# 1-Schematic_N64_SpyDVI.net
KiCad netlist of a schematic drawn in EasyEDA
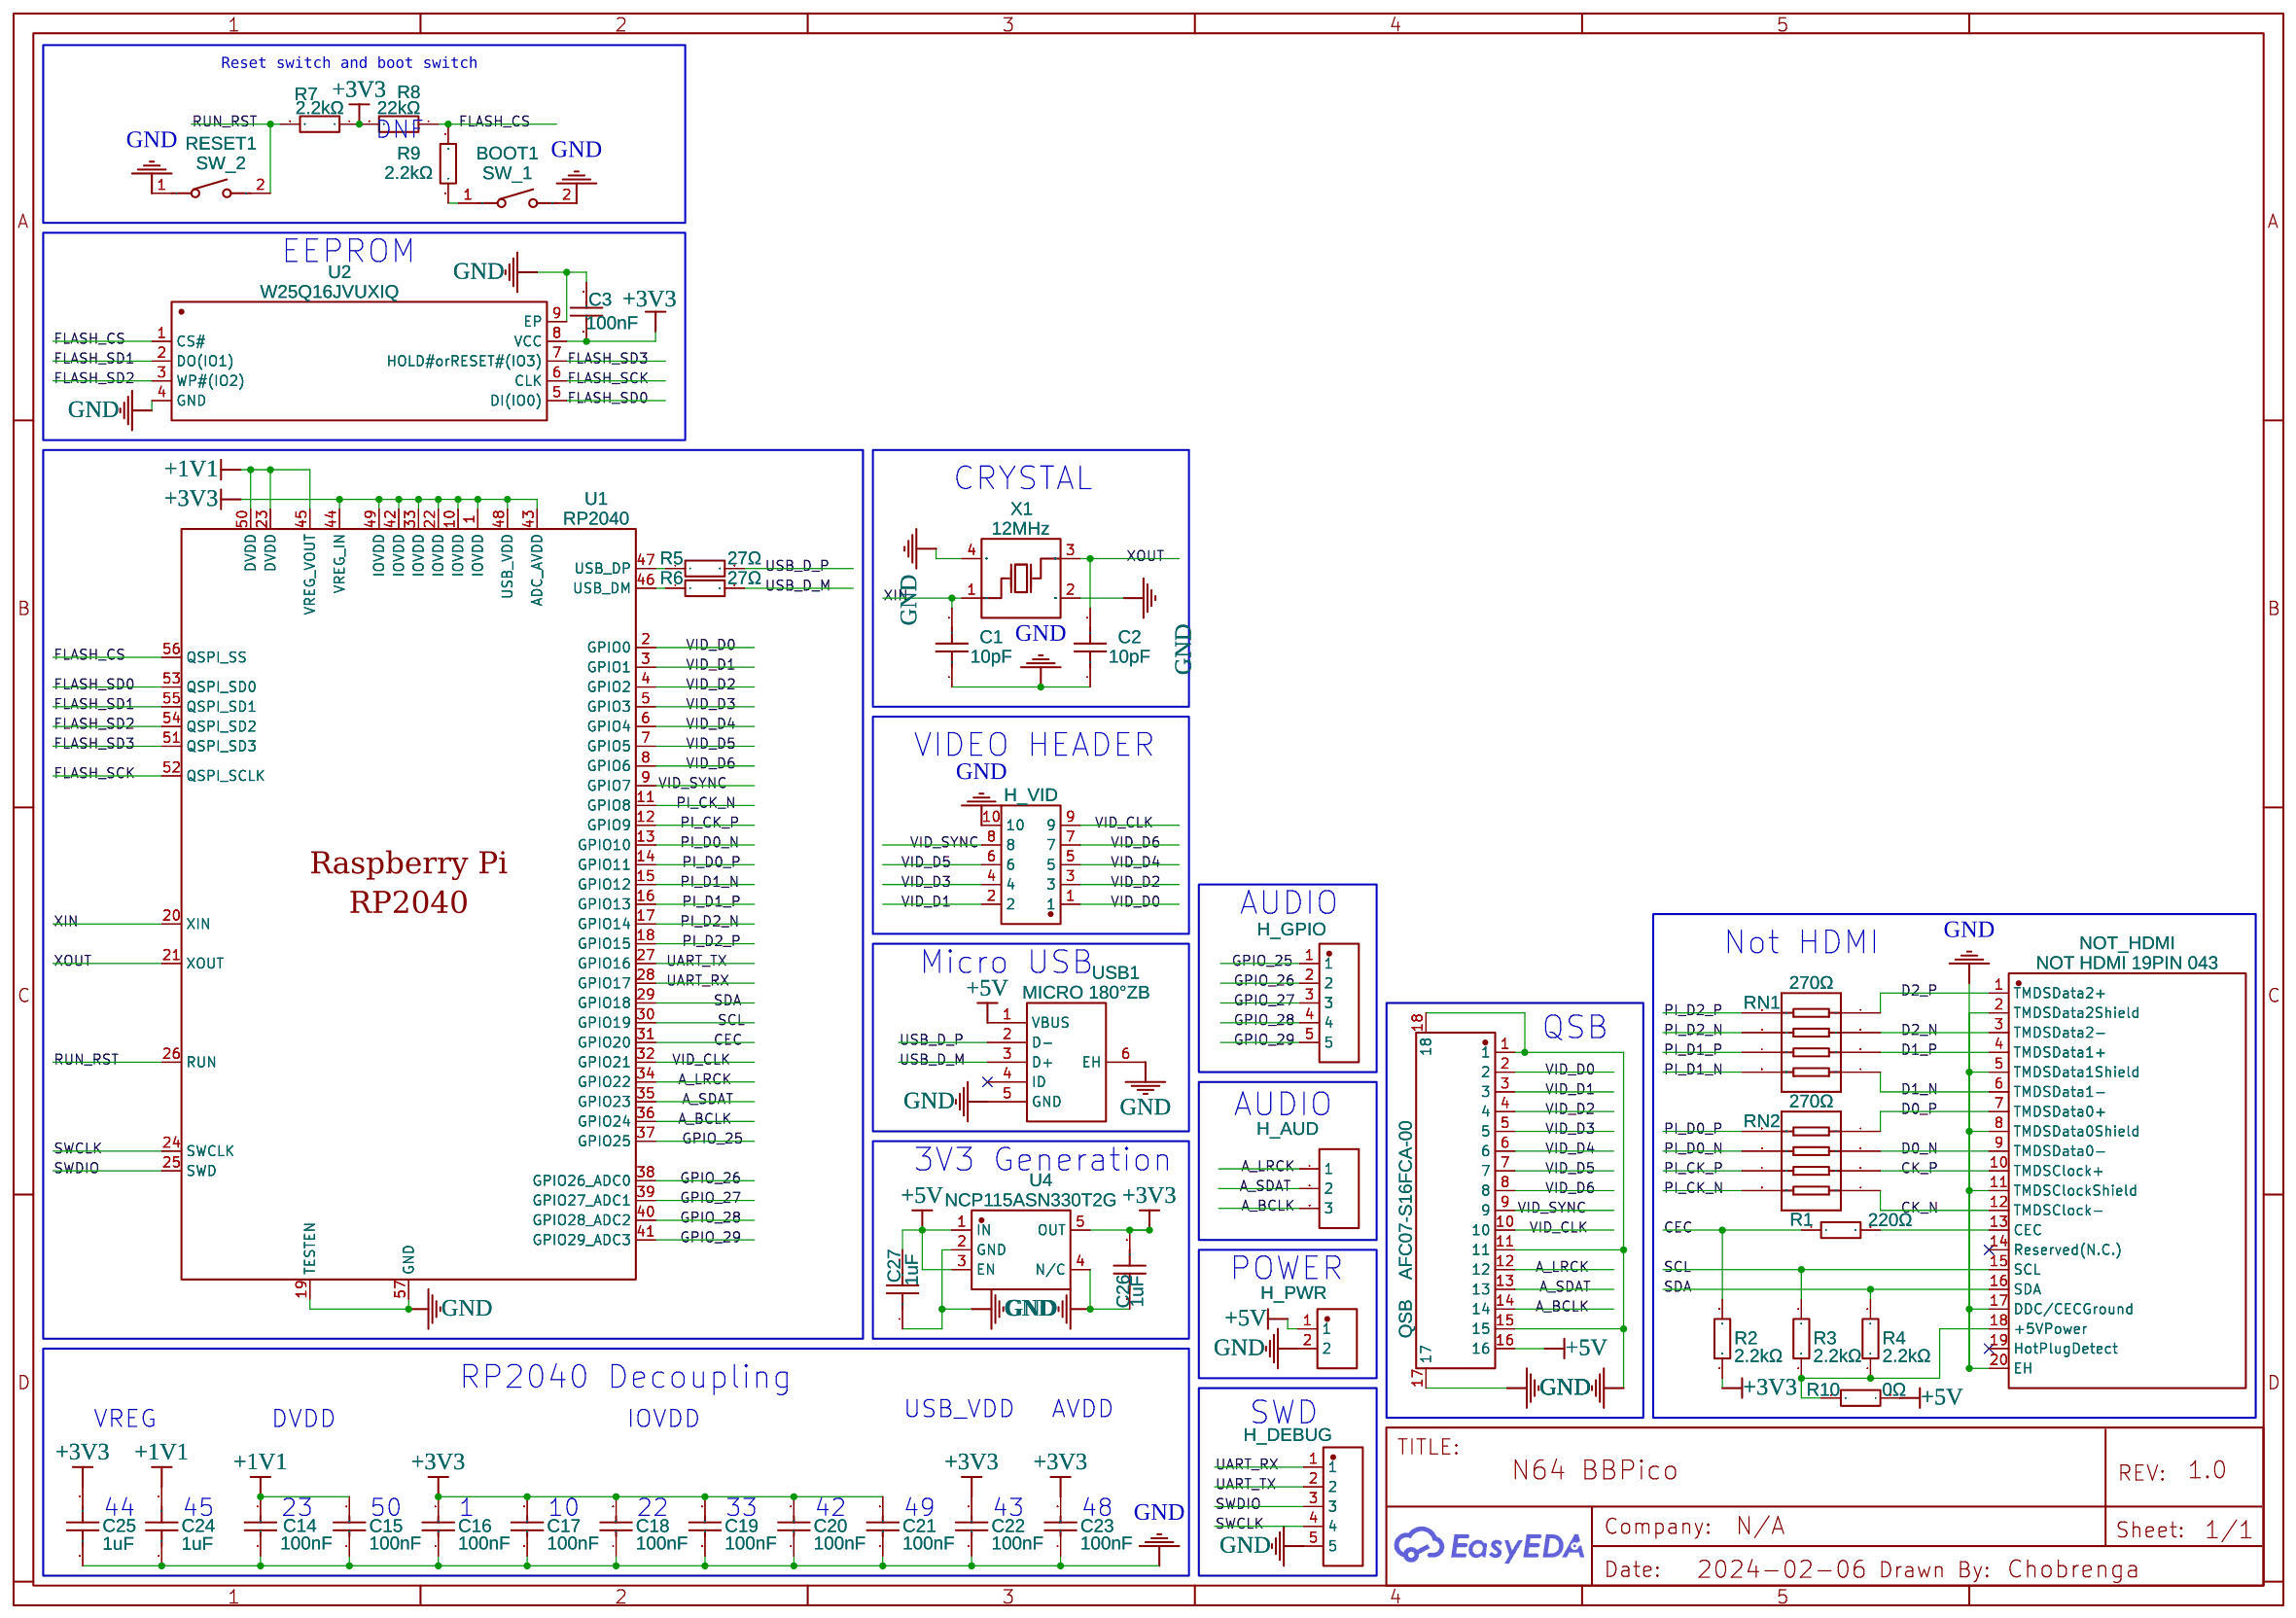
[diagram p0: schematic sheet]

(export (version "E")
  (design (tool "Eeschema 10.0.6"))
  (components
    (comp (ref "BOOT1")
      (value "SW_1")
      (fields (field (name "Manufacturer Part") "TS-1088-AR02016") (field (name "Manufacturer") "XUNPU(讯普)"))
      (libsource (lib "") (part "TS-1088-AR02016_1"))
    )
    (comp (ref "C1")
      (value "10pF")
      (fields
        (field (name "Manufacturer Part") "CL05C100JB5NNNC")
        (field (name "Manufacturer") "SAMSUNG(三星)")
      )
      (libsource (lib "") (part "CL05C100JB5NNNC"))
    )
    (comp (ref "C2")
      (value "10pF")
      (fields
        (field (name "Manufacturer Part") "CL05C100JB5NNNC")
        (field (name "Manufacturer") "SAMSUNG(三星)")
      )
      (libsource (lib "") (part "CL05C100JB5NNNC"))
    )
    (comp (ref "C3")
      (value "100nF")
      (fields
        (field (name "Manufacturer Part") "CL05B104KO5NNNC")
        (field (name "Manufacturer") "SAMSUNG(三星)")
      )
      (libsource (lib "") (part "CL05B104KO5NNNC"))
    )
    (comp (ref "C14")
      (value "100nF")
      (fields
        (field (name "Manufacturer Part") "CL05B104KO5NNNC")
        (field (name "Manufacturer") "SAMSUNG(三星)")
      )
      (libsource (lib "") (part "CL05B104KO5NNNC"))
    )
    (comp (ref "C15")
      (value "100nF")
      (fields
        (field (name "Manufacturer Part") "CL05B104KO5NNNC")
        (field (name "Manufacturer") "SAMSUNG(三星)")
      )
      (libsource (lib "") (part "CL05B104KO5NNNC"))
    )
    (comp (ref "C16")
      (value "100nF")
      (fields
        (field (name "Manufacturer Part") "CL05B104KO5NNNC")
        (field (name "Manufacturer") "SAMSUNG(三星)")
      )
      (libsource (lib "") (part "CL05B104KO5NNNC"))
    )
    (comp (ref "C17")
      (value "100nF")
      (fields
        (field (name "Manufacturer Part") "CL05B104KO5NNNC")
        (field (name "Manufacturer") "SAMSUNG(三星)")
      )
      (libsource (lib "") (part "CL05B104KO5NNNC"))
    )
    (comp (ref "C18")
      (value "100nF")
      (fields
        (field (name "Manufacturer Part") "CL05B104KO5NNNC")
        (field (name "Manufacturer") "SAMSUNG(三星)")
      )
      (libsource (lib "") (part "CL05B104KO5NNNC"))
    )
    (comp (ref "C19")
      (value "100nF")
      (fields
        (field (name "Manufacturer Part") "CL05B104KO5NNNC")
        (field (name "Manufacturer") "SAMSUNG(三星)")
      )
      (libsource (lib "") (part "CL05B104KO5NNNC"))
    )
    (comp (ref "C20")
      (value "100nF")
      (fields
        (field (name "Manufacturer Part") "CL05B104KO5NNNC")
        (field (name "Manufacturer") "SAMSUNG(三星)")
      )
      (libsource (lib "") (part "CL05B104KO5NNNC"))
    )
    (comp (ref "C21")
      (value "100nF")
      (fields
        (field (name "Manufacturer Part") "CL05B104KO5NNNC")
        (field (name "Manufacturer") "SAMSUNG(三星)")
      )
      (libsource (lib "") (part "CL05B104KO5NNNC"))
    )
    (comp (ref "C22")
      (value "100nF")
      (fields
        (field (name "Manufacturer Part") "CL05B104KO5NNNC")
        (field (name "Manufacturer") "SAMSUNG(三星)")
      )
      (libsource (lib "") (part "CL05B104KO5NNNC"))
    )
    (comp (ref "C23")
      (value "100nF")
      (fields
        (field (name "Manufacturer Part") "CL05B104KO5NNNC")
        (field (name "Manufacturer") "SAMSUNG(三星)")
      )
      (libsource (lib "") (part "CL05B104KO5NNNC"))
    )
    (comp (ref "C24")
      (value "1uF")
      (fields
        (field (name "Manufacturer Part") "TCC0402X5R105K100AT")
        (field (name "Manufacturer") "CCTC(三环)")
      )
      (libsource (lib "") (part "TCC0402X5R105K100AT"))
    )
    (comp (ref "C25")
      (value "1uF")
      (fields
        (field (name "Manufacturer Part") "TCC0402X5R105K100AT")
        (field (name "Manufacturer") "CCTC(三环)")
      )
      (libsource (lib "") (part "TCC0402X5R105K100AT"))
    )
    (comp (ref "C26")
      (value "1uF")
      (fields
        (field (name "Manufacturer Part") "TCC0402X5R105K100AT")
        (field (name "Manufacturer") "CCTC(三环)")
      )
      (libsource (lib "") (part "TCC0402X5R105K100AT"))
    )
    (comp (ref "C27")
      (value "1uF")
      (fields
        (field (name "Manufacturer Part") "TCC0402X5R105K100AT")
        (field (name "Manufacturer") "CCTC(三环)")
      )
      (libsource (lib "") (part "TCC0402X5R105K100AT"))
    )
    (comp (ref "H_AUD")
      (value "Header-Male-2.54_1x3")
      (fields (field (name "Manufacturer Part") "2.54-1*3P针") (field (name "Manufacturer") "BOOMELE(博穆精密)"))
      (libsource (lib "") (part "Header-Male-2.54_1x3"))
    )
    (comp (ref "H_DEBUG")
      (value "PZ254V-11-05P")
      (fields (field (name "Manufacturer") "XFCN(兴飞)"))
      (libsource (lib "") (part "PZ254V-11-05P"))
    )
    (comp (ref "H_GPIO")
      (value "PZ254V-11-05P")
      (fields (field (name "Manufacturer") "XFCN(兴飞)"))
      (libsource (lib "") (part "PZ254V-11-05P_1"))
    )
    (comp (ref "H_PWR")
      (value "PZ254V-11-02P")
      (fields (field (name "Manufacturer") "XFCN(兴飞)"))
      (libsource (lib "") (part "PZ254V-11-02P"))
    )
    (comp (ref "H_VID")
      (value "PZ254V-12-10P")
      (fields (field (name "Manufacturer") "XFCN(兴飞)"))
      (libsource (lib "") (part "PZ254V-12-10P"))
    )
    (comp (ref "NOT_HDMI")
      (value "NOT HDMI 19PIN 043")
      (fields
        (field (name "Manufacturer Part") "HDMI 19PIN 043")
        (field (name "Manufacturer") "SHOU HAN(首韩)")
      )
      (libsource (lib "") (part "HDMI 19PIN 043"))
    )
    (comp (ref "QSB")
      (value "AFC07-S16FCA-00")
      (fields (field (name "Manufacturer") "JS(钜硕电子)"))
      (libsource (lib "") (part "AFC07-S16FCA-00"))
    )
    (comp (ref "R1")
      (value "220Ω")
      (fields
        (field (name "Manufacturer Part") "0402WGF2200TCE")
        (field (name "Manufacturer") "UNI-ROYAL(厚声)")
      )
      (libsource (lib "") (part "0402WGF2200TCE"))
    )
    (comp (ref "R2")
      (value "2.2kΩ")
      (fields
        (field (name "Manufacturer Part") "0402WGF2201TCE")
        (field (name "Manufacturer") "UNI-ROYAL(厚声)")
      )
      (libsource (lib "") (part "0402WGF2201TCE"))
    )
    (comp (ref "R3")
      (value "2.2kΩ")
      (fields
        (field (name "Manufacturer Part") "0402WGF2201TCE")
        (field (name "Manufacturer") "UNI-ROYAL(厚声)")
      )
      (libsource (lib "") (part "0402WGF2201TCE"))
    )
    (comp (ref "R4")
      (value "2.2kΩ")
      (fields
        (field (name "Manufacturer Part") "0402WGF2201TCE")
        (field (name "Manufacturer") "UNI-ROYAL(厚声)")
      )
      (libsource (lib "") (part "0402WGF2201TCE"))
    )
    (comp (ref "R5")
      (value "27Ω")
      (fields
        (field (name "Manufacturer Part") "0402WGF270JTCE")
        (field (name "Manufacturer") "UNI-ROYAL(厚声)")
      )
      (libsource (lib "") (part "0402WGF270JTCE"))
    )
    (comp (ref "R6")
      (value "27Ω")
      (fields
        (field (name "Manufacturer Part") "0402WGF270JTCE")
        (field (name "Manufacturer") "UNI-ROYAL(厚声)")
      )
      (libsource (lib "") (part "0402WGF270JTCE"))
    )
    (comp (ref "R7")
      (value "2.2kΩ")
      (fields
        (field (name "Manufacturer Part") "0402WGF2201TCE")
        (field (name "Manufacturer") "UNI-ROYAL(厚声)")
      )
      (libsource (lib "") (part "0402WGF2201TCE_1"))
    )
    (comp (ref "R8") (value "22kΩ") (libsource (lib "") (part "0402WGF2202TCE")))
    (comp (ref "R9")
      (value "2.2kΩ")
      (fields
        (field (name "Manufacturer Part") "0402WGF2201TCE")
        (field (name "Manufacturer") "UNI-ROYAL(厚声)")
      )
      (libsource (lib "") (part "0402WGF2201TCE"))
    )
    (comp (ref "R10")
      (value "0Ω")
      (fields
        (field (name "Manufacturer Part") "0603WAF0000T5E")
        (field (name "Manufacturer") "UNI-ROYAL(厚声)")
      )
      (libsource (lib "") (part "0603WAF0000T5E"))
    )
    (comp (ref "RESET1")
      (value "SW_2")
      (fields (field (name "Manufacturer Part") "TS-1088-AR02016") (field (name "Manufacturer") "XUNPU(讯普)"))
      (libsource (lib "") (part "TS-1088-AR02016"))
    )
    (comp (ref "RN1")
      (value "270Ω")
      (fields (field (name "Manufacturer Part") "CAT10-271J4LF") (field (name "Manufacturer") "BOURNS"))
      (libsource (lib "") (part "CAT10-271J4LF"))
    )
    (comp (ref "RN2")
      (value "270Ω")
      (fields (field (name "Manufacturer Part") "CAT10-271J4LF") (field (name "Manufacturer") "BOURNS"))
      (libsource (lib "") (part "CAT10-271J4LF"))
    )
    (comp (ref "U1")
      (value "RP2040")
      (fields (field (name "Manufacturer") "Raspberry Pi(树莓派)"))
      (libsource (lib "") (part "RP2040"))
    )
    (comp (ref "U2")
      (value "W25Q16JVUXIQ")
      (fields (field (name "Manufacturer") "WINBOND(华邦)"))
      (libsource (lib "") (part "W25Q16JVUXIQ"))
    )
    (comp (ref "U4")
      (value "NCP115ASN330T2G")
      (fields (field (name "Manufacturer") "onsemi(安森美)"))
      (libsource (lib "") (part "NCP115ASN330T2G"))
    )
    (comp (ref "USB1")
      (value "MICRO 180°ZB")
      (fields (field (name "Manufacturer") "SHOU HAN(首韩)"))
      (libsource (lib "") (part "MICRO 180°ZB"))
    )
    (comp (ref "X1")
      (value "12MHz")
      (fields (field (name "Manufacturer Part") "X322512MMB4SI") (field (name "Manufacturer") "YXC(扬兴晶振)"))
      (libsource (lib "") (part "X322512MMB4SI"))
    )
  )
  (nets
    (net (code "1") (name "+1V1") (class "Default")
      (node (ref "C14") (pin "2") (pinfunction "2_2") (pintype "input"))
      (node (ref "C15") (pin "2") (pinfunction "2_2") (pintype "input"))
      (node (ref "C24") (pin "2") (pinfunction "2_2") (pintype "unspecified"))
      (node (ref "U1") (pin "23") (pinfunction "DVDD_23") (pintype "bidirectional"))
      (node (ref "U1") (pin "45") (pinfunction "VREG_VOUT_45") (pintype "bidirectional"))
      (node (ref "U1") (pin "50") (pinfunction "DVDD_50") (pintype "bidirectional"))
    )
    (net (code "2") (name "+3V3") (class "Default")
      (node (ref "C16") (pin "2") (pinfunction "2_2") (pintype "input"))
      (node (ref "C17") (pin "2") (pinfunction "2_2") (pintype "input"))
      (node (ref "C18") (pin "2") (pinfunction "2_2") (pintype "input"))
      (node (ref "C19") (pin "2") (pinfunction "2_2") (pintype "input"))
      (node (ref "C20") (pin "2") (pinfunction "2_2") (pintype "input"))
      (node (ref "C21") (pin "2") (pinfunction "2_2") (pintype "input"))
      (node (ref "C22") (pin "2") (pinfunction "2_2") (pintype "input"))
      (node (ref "C23") (pin "2") (pinfunction "2_2") (pintype "input"))
      (node (ref "C25") (pin "2") (pinfunction "2_2") (pintype "unspecified"))
      (node (ref "C26") (pin "2") (pinfunction "2_2") (pintype "unspecified"))
      (node (ref "C3") (pin "1") (pinfunction "1_1") (pintype "input"))
      (node (ref "R2") (pin "1") (pinfunction "1_1") (pintype "input"))
      (node (ref "R7") (pin "1") (pinfunction "1_1") (pintype "input"))
      (node (ref "R8") (pin "2") (pinfunction "2_2") (pintype "input"))
      (node (ref "U1") (pin "1") (pinfunction "IOVDD_1") (pintype "bidirectional"))
      (node (ref "U1") (pin "10") (pinfunction "IOVDD_10") (pintype "bidirectional"))
      (node (ref "U1") (pin "22") (pinfunction "IOVDD_22") (pintype "bidirectional"))
      (node (ref "U1") (pin "33") (pinfunction "IOVDD_33") (pintype "bidirectional"))
      (node (ref "U1") (pin "42") (pinfunction "IOVDD_42") (pintype "bidirectional"))
      (node (ref "U1") (pin "43") (pinfunction "ADC_AVDD_43") (pintype "bidirectional"))
      (node (ref "U1") (pin "44") (pinfunction "VREG_IN_44") (pintype "bidirectional"))
      (node (ref "U1") (pin "48") (pinfunction "USB_VDD_48") (pintype "bidirectional"))
      (node (ref "U1") (pin "49") (pinfunction "IOVDD_49") (pintype "bidirectional"))
      (node (ref "U2") (pin "8") (pinfunction "VCC_8") (pintype "unspecified"))
      (node (ref "U4") (pin "5") (pinfunction "OUT_5") (pintype "unspecified"))
    )
    (net (code "3") (name "+5V") (class "Default")
      (node (ref "C27") (pin "2") (pinfunction "2_2") (pintype "unspecified"))
      (node (ref "H_PWR") (pin "1") (pinfunction "1_1") (pintype "unspecified"))
      (node (ref "QSB") (pin "16") (pinfunction "16_16") (pintype "unspecified"))
      (node (ref "R10") (pin "1") (pinfunction "1_1") (pintype "input"))
      (node (ref "U4") (pin "1") (pinfunction "IN_1") (pintype "unspecified"))
      (node (ref "U4") (pin "3") (pinfunction "EN_3") (pintype "unspecified"))
      (node (ref "USB1") (pin "1") (pinfunction "VBUS_1") (pintype "unspecified"))
    )
    (net (code "4") (name "/A_BCLK") (class "Default")
      (node (ref "H_AUD") (pin "3") (pinfunction "3_3") (pintype "input"))
      (node (ref "QSB") (pin "14") (pinfunction "14_14") (pintype "unspecified"))
      (node (ref "U1") (pin "36") (pinfunction "GPIO24_36") (pintype "bidirectional"))
    )
    (net (code "5") (name "/A_LRCK") (class "Default")
      (node (ref "H_AUD") (pin "1") (pinfunction "1_1") (pintype "input"))
      (node (ref "QSB") (pin "12") (pinfunction "12_12") (pintype "unspecified"))
      (node (ref "U1") (pin "34") (pinfunction "GPIO22_34") (pintype "bidirectional"))
    )
    (net (code "6") (name "/A_SDAT") (class "Default")
      (node (ref "H_AUD") (pin "2") (pinfunction "2_2") (pintype "input"))
      (node (ref "QSB") (pin "13") (pinfunction "13_13") (pintype "unspecified"))
      (node (ref "U1") (pin "35") (pinfunction "GPIO23_35") (pintype "bidirectional"))
    )
    (net (code "7") (name "/CEC") (class "Default")
      (node (ref "R1") (pin "1") (pinfunction "1_1") (pintype "input"))
      (node (ref "R2") (pin "2") (pinfunction "2_2") (pintype "input"))
      (node (ref "U1") (pin "31") (pinfunction "GPIO20_31") (pintype "bidirectional"))
    )
    (net (code "8") (name "/CK_N") (class "Default")
      (node (ref "NOT_HDMI") (pin "12") (pinfunction "TMDSClock-_12") (pintype "unspecified"))
      (node (ref "RN2") (pin "1") (pinfunction "1_1") (pintype "input"))
    )
    (net (code "9") (name "/CK_P") (class "Default")
      (node (ref "NOT_HDMI") (pin "10") (pinfunction "TMDSClock+_10") (pintype "unspecified"))
      (node (ref "RN2") (pin "2") (pinfunction "2_2") (pintype "input"))
    )
    (net (code "10") (name "/D0_N") (class "Default")
      (node (ref "NOT_HDMI") (pin "9") (pinfunction "TMDSData0-_9") (pintype "unspecified"))
      (node (ref "RN2") (pin "3") (pinfunction "3_3") (pintype "input"))
    )
    (net (code "11") (name "/D0_P") (class "Default")
      (node (ref "NOT_HDMI") (pin "7") (pinfunction "TMDSData0+_7") (pintype "unspecified"))
      (node (ref "RN2") (pin "4") (pinfunction "4_4") (pintype "input"))
    )
    (net (code "12") (name "/D1_N") (class "Default")
      (node (ref "NOT_HDMI") (pin "6") (pinfunction "TMDSData1-_6") (pintype "unspecified"))
      (node (ref "RN1") (pin "1") (pinfunction "1_1") (pintype "input"))
    )
    (net (code "13") (name "/D1_P") (class "Default")
      (node (ref "NOT_HDMI") (pin "4") (pinfunction "TMDSData1+_4") (pintype "unspecified"))
      (node (ref "RN1") (pin "2") (pinfunction "2_2") (pintype "input"))
    )
    (net (code "14") (name "/D2_N") (class "Default")
      (node (ref "NOT_HDMI") (pin "3") (pinfunction "TMDSData2-_3") (pintype "unspecified"))
      (node (ref "RN1") (pin "3") (pinfunction "3_3") (pintype "input"))
    )
    (net (code "15") (name "/D2_P") (class "Default")
      (node (ref "NOT_HDMI") (pin "1") (pinfunction "TMDSData2+_1") (pintype "unspecified"))
      (node (ref "RN1") (pin "4") (pinfunction "4_4") (pintype "input"))
    )
    (net (code "16") (name "/FLASH_CS") (class "Default")
      (node (ref "R8") (pin "1") (pinfunction "1_1") (pintype "input"))
      (node (ref "R9") (pin "2") (pinfunction "2_2") (pintype "input"))
      (node (ref "U1") (pin "56") (pinfunction "QSPI_SS_56") (pintype "bidirectional"))
      (node (ref "U2") (pin "1") (pinfunction "CS#_1") (pintype "unspecified"))
    )
    (net (code "17") (name "/FLASH_SCK") (class "Default")
      (node (ref "U1") (pin "52") (pinfunction "QSPI_SCLK_52") (pintype "output"))
      (node (ref "U2") (pin "6") (pinfunction "CLK_6") (pintype "unspecified"))
    )
    (net (code "18") (name "/FLASH_SD0") (class "Default")
      (node (ref "U1") (pin "53") (pinfunction "QSPI_SD0_53") (pintype "bidirectional"))
      (node (ref "U2") (pin "5") (pinfunction "DI(IO0)_5") (pintype "unspecified"))
    )
    (net (code "19") (name "/FLASH_SD1") (class "Default")
      (node (ref "U1") (pin "55") (pinfunction "QSPI_SD1_55") (pintype "bidirectional"))
      (node (ref "U2") (pin "2") (pinfunction "DO(IO1)_2") (pintype "unspecified"))
    )
    (net (code "20") (name "/FLASH_SD2") (class "Default")
      (node (ref "U1") (pin "54") (pinfunction "QSPI_SD2_54") (pintype "bidirectional"))
      (node (ref "U2") (pin "3") (pinfunction "WP#(IO2)_3") (pintype "unspecified"))
    )
    (net (code "21") (name "/FLASH_SD3") (class "Default")
      (node (ref "U1") (pin "51") (pinfunction "QSPI_SD3_51") (pintype "bidirectional"))
      (node (ref "U2") (pin "7") (pinfunction "HOLD#orRESET#(IO3)_7") (pintype "unspecified"))
    )
    (net (code "22") (name "/GPIO_25") (class "Default")
      (node (ref "H_GPIO") (pin "1") (pinfunction "1_1") (pintype "unspecified"))
      (node (ref "U1") (pin "37") (pinfunction "GPIO25_37") (pintype "bidirectional"))
    )
    (net (code "23") (name "/GPIO_26") (class "Default")
      (node (ref "H_GPIO") (pin "2") (pinfunction "2_2") (pintype "unspecified"))
      (node (ref "U1") (pin "38") (pinfunction "GPIO26_ADC0_38") (pintype "bidirectional"))
    )
    (net (code "24") (name "/GPIO_27") (class "Default")
      (node (ref "H_GPIO") (pin "3") (pinfunction "3_3") (pintype "unspecified"))
      (node (ref "U1") (pin "39") (pinfunction "GPIO27_ADC1_39") (pintype "bidirectional"))
    )
    (net (code "25") (name "/GPIO_28") (class "Default")
      (node (ref "H_GPIO") (pin "4") (pinfunction "4_4") (pintype "unspecified"))
      (node (ref "U1") (pin "40") (pinfunction "GPIO28_ADC2_40") (pintype "bidirectional"))
    )
    (net (code "26") (name "/GPIO_29") (class "Default")
      (node (ref "H_GPIO") (pin "5") (pinfunction "5_5") (pintype "unspecified"))
      (node (ref "U1") (pin "41") (pinfunction "GPIO29_ADC3_41") (pintype "bidirectional"))
    )
    (net (code "27") (name "/PI_CK_N") (class "Default")
      (node (ref "RN2") (pin "8") (pinfunction "8_8") (pintype "input"))
      (node (ref "U1") (pin "11") (pinfunction "GPIO8_11") (pintype "bidirectional"))
    )
    (net (code "28") (name "/PI_CK_P") (class "Default")
      (node (ref "RN2") (pin "7") (pinfunction "7_7") (pintype "input"))
      (node (ref "U1") (pin "12") (pinfunction "GPIO9_12") (pintype "bidirectional"))
    )
    (net (code "29") (name "/PI_D0_N") (class "Default")
      (node (ref "RN2") (pin "6") (pinfunction "6_6") (pintype "input"))
      (node (ref "U1") (pin "13") (pinfunction "GPIO10_13") (pintype "bidirectional"))
    )
    (net (code "30") (name "/PI_D0_P") (class "Default")
      (node (ref "RN2") (pin "5") (pinfunction "5_5") (pintype "input"))
      (node (ref "U1") (pin "14") (pinfunction "GPIO11_14") (pintype "bidirectional"))
    )
    (net (code "31") (name "/PI_D1_N") (class "Default")
      (node (ref "RN1") (pin "8") (pinfunction "8_8") (pintype "input"))
      (node (ref "U1") (pin "15") (pinfunction "GPIO12_15") (pintype "bidirectional"))
    )
    (net (code "32") (name "/PI_D1_P") (class "Default")
      (node (ref "RN1") (pin "7") (pinfunction "7_7") (pintype "input"))
      (node (ref "U1") (pin "16") (pinfunction "GPIO13_16") (pintype "bidirectional"))
    )
    (net (code "33") (name "/PI_D2_N") (class "Default")
      (node (ref "RN1") (pin "6") (pinfunction "6_6") (pintype "input"))
      (node (ref "U1") (pin "17") (pinfunction "GPIO14_17") (pintype "bidirectional"))
    )
    (net (code "34") (name "/PI_D2_P") (class "Default")
      (node (ref "RN1") (pin "5") (pinfunction "5_5") (pintype "input"))
      (node (ref "U1") (pin "18") (pinfunction "GPIO15_18") (pintype "bidirectional"))
    )
    (net (code "35") (name "/RUN_RST") (class "Default")
      (node (ref "R7") (pin "2") (pinfunction "2_2") (pintype "input"))
      (node (ref "RESET1") (pin "2") (pinfunction "2_2") (pintype "unspecified"))
      (node (ref "U1") (pin "26") (pinfunction "RUN_26") (pintype "input"))
    )
    (net (code "36") (name "/SCL") (class "Default")
      (node (ref "NOT_HDMI") (pin "15") (pinfunction "SCL_15") (pintype "unspecified"))
      (node (ref "R3") (pin "2") (pinfunction "2_2") (pintype "input"))
      (node (ref "U1") (pin "30") (pinfunction "GPIO19_30") (pintype "bidirectional"))
    )
    (net (code "37") (name "/SDA") (class "Default")
      (node (ref "NOT_HDMI") (pin "16") (pinfunction "SDA_16") (pintype "unspecified"))
      (node (ref "R4") (pin "2") (pinfunction "2_2") (pintype "input"))
      (node (ref "U1") (pin "29") (pinfunction "GPIO18_29") (pintype "bidirectional"))
    )
    (net (code "38") (name "/SWCLK") (class "Default")
      (node (ref "H_DEBUG") (pin "4") (pinfunction "4_4") (pintype "unspecified"))
      (node (ref "U1") (pin "24") (pinfunction "SWCLK_24") (pintype "output"))
    )
    (net (code "39") (name "/SWDIO") (class "Default")
      (node (ref "H_DEBUG") (pin "3") (pinfunction "3_3") (pintype "unspecified"))
      (node (ref "U1") (pin "25") (pinfunction "SWD_25") (pintype "bidirectional"))
    )
    (net (code "40") (name "/UART_RX") (class "Default")
      (node (ref "H_DEBUG") (pin "1") (pinfunction "1_1") (pintype "unspecified"))
      (node (ref "U1") (pin "28") (pinfunction "GPIO17_28") (pintype "bidirectional"))
    )
    (net (code "41") (name "/UART_TX") (class "Default")
      (node (ref "H_DEBUG") (pin "2") (pinfunction "2_2") (pintype "unspecified"))
      (node (ref "U1") (pin "27") (pinfunction "GPIO16_27") (pintype "bidirectional"))
    )
    (net (code "42") (name "/USB_D_M") (class "Default")
      (node (ref "R6") (pin "2") (pinfunction "2_2") (pintype "input"))
      (node (ref "USB1") (pin "3") (pinfunction "D+_3") (pintype "unspecified"))
    )
    (net (code "43") (name "/USB_D_P") (class "Default")
      (node (ref "R5") (pin "2") (pinfunction "2_2") (pintype "input"))
      (node (ref "USB1") (pin "2") (pinfunction "D-_2") (pintype "unspecified"))
    )
    (net (code "44") (name "/VID_CLK") (class "Default")
      (node (ref "H_VID") (pin "9") (pinfunction "9_9") (pintype "unspecified"))
      (node (ref "QSB") (pin "10") (pinfunction "10_10") (pintype "unspecified"))
      (node (ref "U1") (pin "32") (pinfunction "GPIO21_32") (pintype "bidirectional"))
    )
    (net (code "45") (name "/VID_D0") (class "Default")
      (node (ref "H_VID") (pin "1") (pinfunction "1_1") (pintype "unspecified"))
      (node (ref "QSB") (pin "2") (pinfunction "2_2") (pintype "unspecified"))
      (node (ref "U1") (pin "2") (pinfunction "GPIO0_2") (pintype "bidirectional"))
    )
    (net (code "46") (name "/VID_D1") (class "Default")
      (node (ref "H_VID") (pin "2") (pinfunction "2_2") (pintype "unspecified"))
      (node (ref "QSB") (pin "3") (pinfunction "3_3") (pintype "unspecified"))
      (node (ref "U1") (pin "3") (pinfunction "GPIO1_3") (pintype "bidirectional"))
    )
    (net (code "47") (name "/VID_D2") (class "Default")
      (node (ref "H_VID") (pin "3") (pinfunction "3_3") (pintype "unspecified"))
      (node (ref "QSB") (pin "4") (pinfunction "4_4") (pintype "unspecified"))
      (node (ref "U1") (pin "4") (pinfunction "GPIO2_4") (pintype "bidirectional"))
    )
    (net (code "48") (name "/VID_D3") (class "Default")
      (node (ref "H_VID") (pin "4") (pinfunction "4_4") (pintype "unspecified"))
      (node (ref "QSB") (pin "5") (pinfunction "5_5") (pintype "unspecified"))
      (node (ref "U1") (pin "5") (pinfunction "GPIO3_5") (pintype "bidirectional"))
    )
    (net (code "49") (name "/VID_D4") (class "Default")
      (node (ref "H_VID") (pin "5") (pinfunction "5_5") (pintype "unspecified"))
      (node (ref "QSB") (pin "6") (pinfunction "6_6") (pintype "unspecified"))
      (node (ref "U1") (pin "6") (pinfunction "GPIO4_6") (pintype "bidirectional"))
    )
    (net (code "50") (name "/VID_D5") (class "Default")
      (node (ref "H_VID") (pin "6") (pinfunction "6_6") (pintype "unspecified"))
      (node (ref "QSB") (pin "7") (pinfunction "7_7") (pintype "unspecified"))
      (node (ref "U1") (pin "7") (pinfunction "GPIO5_7") (pintype "bidirectional"))
    )
    (net (code "51") (name "/VID_D6") (class "Default")
      (node (ref "H_VID") (pin "7") (pinfunction "7_7") (pintype "unspecified"))
      (node (ref "QSB") (pin "8") (pinfunction "8_8") (pintype "unspecified"))
      (node (ref "U1") (pin "8") (pinfunction "GPIO6_8") (pintype "bidirectional"))
    )
    (net (code "52") (name "/VID_SYNC") (class "Default")
      (node (ref "H_VID") (pin "8") (pinfunction "8_8") (pintype "unspecified"))
      (node (ref "QSB") (pin "9") (pinfunction "9_9") (pintype "unspecified"))
      (node (ref "U1") (pin "9") (pinfunction "GPIO7_9") (pintype "bidirectional"))
    )
    (net (code "53") (name "/XIN") (class "Default")
      (node (ref "C1") (pin "2") (pinfunction "2_2") (pintype "unspecified"))
      (node (ref "U1") (pin "20") (pinfunction "XIN_20") (pintype "input"))
      (node (ref "X1") (pin "1") (pinfunction "OSC1_1") (pintype "unspecified"))
    )
    (net (code "54") (name "/XOUT") (class "Default")
      (node (ref "C2") (pin "2") (pinfunction "2_2") (pintype "unspecified"))
      (node (ref "U1") (pin "21") (pinfunction "XOUT_21") (pintype "unspecified"))
      (node (ref "X1") (pin "3") (pinfunction "OSC2_3") (pintype "unspecified"))
    )
    (net (code "55") (name "GND") (class "Default")
      (node (ref "BOOT1") (pin "2") (pinfunction "2_2") (pintype "unspecified"))
      (node (ref "C1") (pin "1") (pinfunction "1_1") (pintype "unspecified"))
      (node (ref "C14") (pin "1") (pinfunction "1_1") (pintype "input"))
      (node (ref "C15") (pin "1") (pinfunction "1_1") (pintype "input"))
      (node (ref "C16") (pin "1") (pinfunction "1_1") (pintype "input"))
      (node (ref "C17") (pin "1") (pinfunction "1_1") (pintype "input"))
      (node (ref "C18") (pin "1") (pinfunction "1_1") (pintype "input"))
      (node (ref "C19") (pin "1") (pinfunction "1_1") (pintype "input"))
      (node (ref "C2") (pin "1") (pinfunction "1_1") (pintype "unspecified"))
      (node (ref "C20") (pin "1") (pinfunction "1_1") (pintype "input"))
      (node (ref "C21") (pin "1") (pinfunction "1_1") (pintype "input"))
      (node (ref "C22") (pin "1") (pinfunction "1_1") (pintype "input"))
      (node (ref "C23") (pin "1") (pinfunction "1_1") (pintype "input"))
      (node (ref "C24") (pin "1") (pinfunction "1_1") (pintype "unspecified"))
      (node (ref "C25") (pin "1") (pinfunction "1_1") (pintype "unspecified"))
      (node (ref "C26") (pin "1") (pinfunction "1_1") (pintype "unspecified"))
      (node (ref "C27") (pin "1") (pinfunction "1_1") (pintype "unspecified"))
      (node (ref "C3") (pin "2") (pinfunction "2_2") (pintype "input"))
      (node (ref "H_DEBUG") (pin "5") (pinfunction "5_5") (pintype "unspecified"))
      (node (ref "H_PWR") (pin "2") (pinfunction "2_2") (pintype "unspecified"))
      (node (ref "H_VID") (pin "10") (pinfunction "10_10") (pintype "unspecified"))
      (node (ref "NOT_HDMI") (pin "11") (pinfunction "TMDSClockShield_11") (pintype "unspecified"))
      (node (ref "NOT_HDMI") (pin "17") (pinfunction "DDC/CECGround_17") (pintype "unspecified"))
      (node (ref "NOT_HDMI") (pin "2") (pinfunction "TMDSData2Shield_2") (pintype "unspecified"))
      (node (ref "NOT_HDMI") (pin "20") (pinfunction "EH_20") (pintype "unspecified"))
      (node (ref "NOT_HDMI") (pin "5") (pinfunction "TMDSData1Shield_5") (pintype "unspecified"))
      (node (ref "NOT_HDMI") (pin "8") (pinfunction "TMDSData0Shield_8") (pintype "unspecified"))
      (node (ref "QSB") (pin "1") (pinfunction "1_1") (pintype "unspecified"))
      (node (ref "QSB") (pin "11") (pinfunction "11_11") (pintype "unspecified"))
      (node (ref "QSB") (pin "15") (pinfunction "15_15") (pintype "unspecified"))
      (node (ref "QSB") (pin "17") (pinfunction "17_17") (pintype "unspecified"))
      (node (ref "QSB") (pin "18") (pinfunction "18_18") (pintype "unspecified"))
      (node (ref "RESET1") (pin "1") (pinfunction "1_1") (pintype "unspecified"))
      (node (ref "U1") (pin "19") (pinfunction "TESTEN_19") (pintype "unspecified"))
      (node (ref "U1") (pin "57") (pinfunction "GND_57") (pintype "bidirectional"))
      (node (ref "U2") (pin "4") (pinfunction "GND_4") (pintype "unspecified"))
      (node (ref "U2") (pin "9") (pinfunction "EP_9") (pintype "unspecified"))
      (node (ref "U4") (pin "2") (pinfunction "GND_2") (pintype "unspecified"))
      (node (ref "U4") (pin "4") (pinfunction "N/C_4") (pintype "unspecified"))
      (node (ref "USB1") (pin "5") (pinfunction "GND_5") (pintype "unspecified"))
      (node (ref "USB1") (pin "6") (pinfunction "EH_6") (pintype "unspecified"))
      (node (ref "X1") (pin "2") (pinfunction "GND_2") (pintype "unspecified"))
      (node (ref "X1") (pin "4") (pinfunction "GND_4") (pintype "unspecified"))
    )
    (net (code "56") (name "Net-(BOOT1-Pad1)") (class "Default")
      (node (ref "BOOT1") (pin "1") (pinfunction "1_1") (pintype "unspecified"))
      (node (ref "R9") (pin "1") (pinfunction "1_1") (pintype "input"))
    )
    (net (code "57") (name "Net-(NOT_HDMI-+5VPower)") (class "Default")
      (node (ref "NOT_HDMI") (pin "18") (pinfunction "+5VPower_18") (pintype "unspecified"))
      (node (ref "R10") (pin "2") (pinfunction "2_2") (pintype "input"))
      (node (ref "R3") (pin "1") (pinfunction "1_1") (pintype "input"))
      (node (ref "R4") (pin "1") (pinfunction "1_1") (pintype "input"))
    )
    (net (code "58") (name "Net-(NOT_HDMI-CEC)") (class "Default")
      (node (ref "NOT_HDMI") (pin "13") (pinfunction "CEC_13") (pintype "unspecified"))
      (node (ref "R1") (pin "2") (pinfunction "2_2") (pintype "input"))
    )
    (net (code "59") (name "Net-(U1-USB_DM)") (class "Default")
      (node (ref "R6") (pin "1") (pinfunction "1_1") (pintype "input"))
      (node (ref "U1") (pin "46") (pinfunction "USB_DM_46") (pintype "bidirectional"))
    )
    (net (code "60") (name "Net-(U1-USB_DP)") (class "Default")
      (node (ref "R5") (pin "1") (pinfunction "1_1") (pintype "input"))
      (node (ref "U1") (pin "47") (pinfunction "USB_DP_47") (pintype "bidirectional"))
    )
    (net (code "61") (name "unconnected-(NOT_HDMI-HotPlugDetect-Pad19)") (class "Default")
      (node (ref "NOT_HDMI") (pin "19") (pinfunction "HotPlugDetect_19") (pintype "unspecified+no_connect"))
    )
    (net (code "62") (name "unconnected-(NOT_HDMI-Reserved(N.C.)-Pad14)") (class "Default")
      (node (ref "NOT_HDMI") (pin "14") (pinfunction "Reserved(N.C.)_14") (pintype "unspecified+no_connect"))
    )
    (net (code "63") (name "unconnected-(USB1-ID-Pad4)") (class "Default")
      (node (ref "USB1") (pin "4") (pinfunction "ID_4") (pintype "unspecified+no_connect"))
    )
  )
)
